# buffer.net
KiCad netlist of a schematic drawn in EAGLE
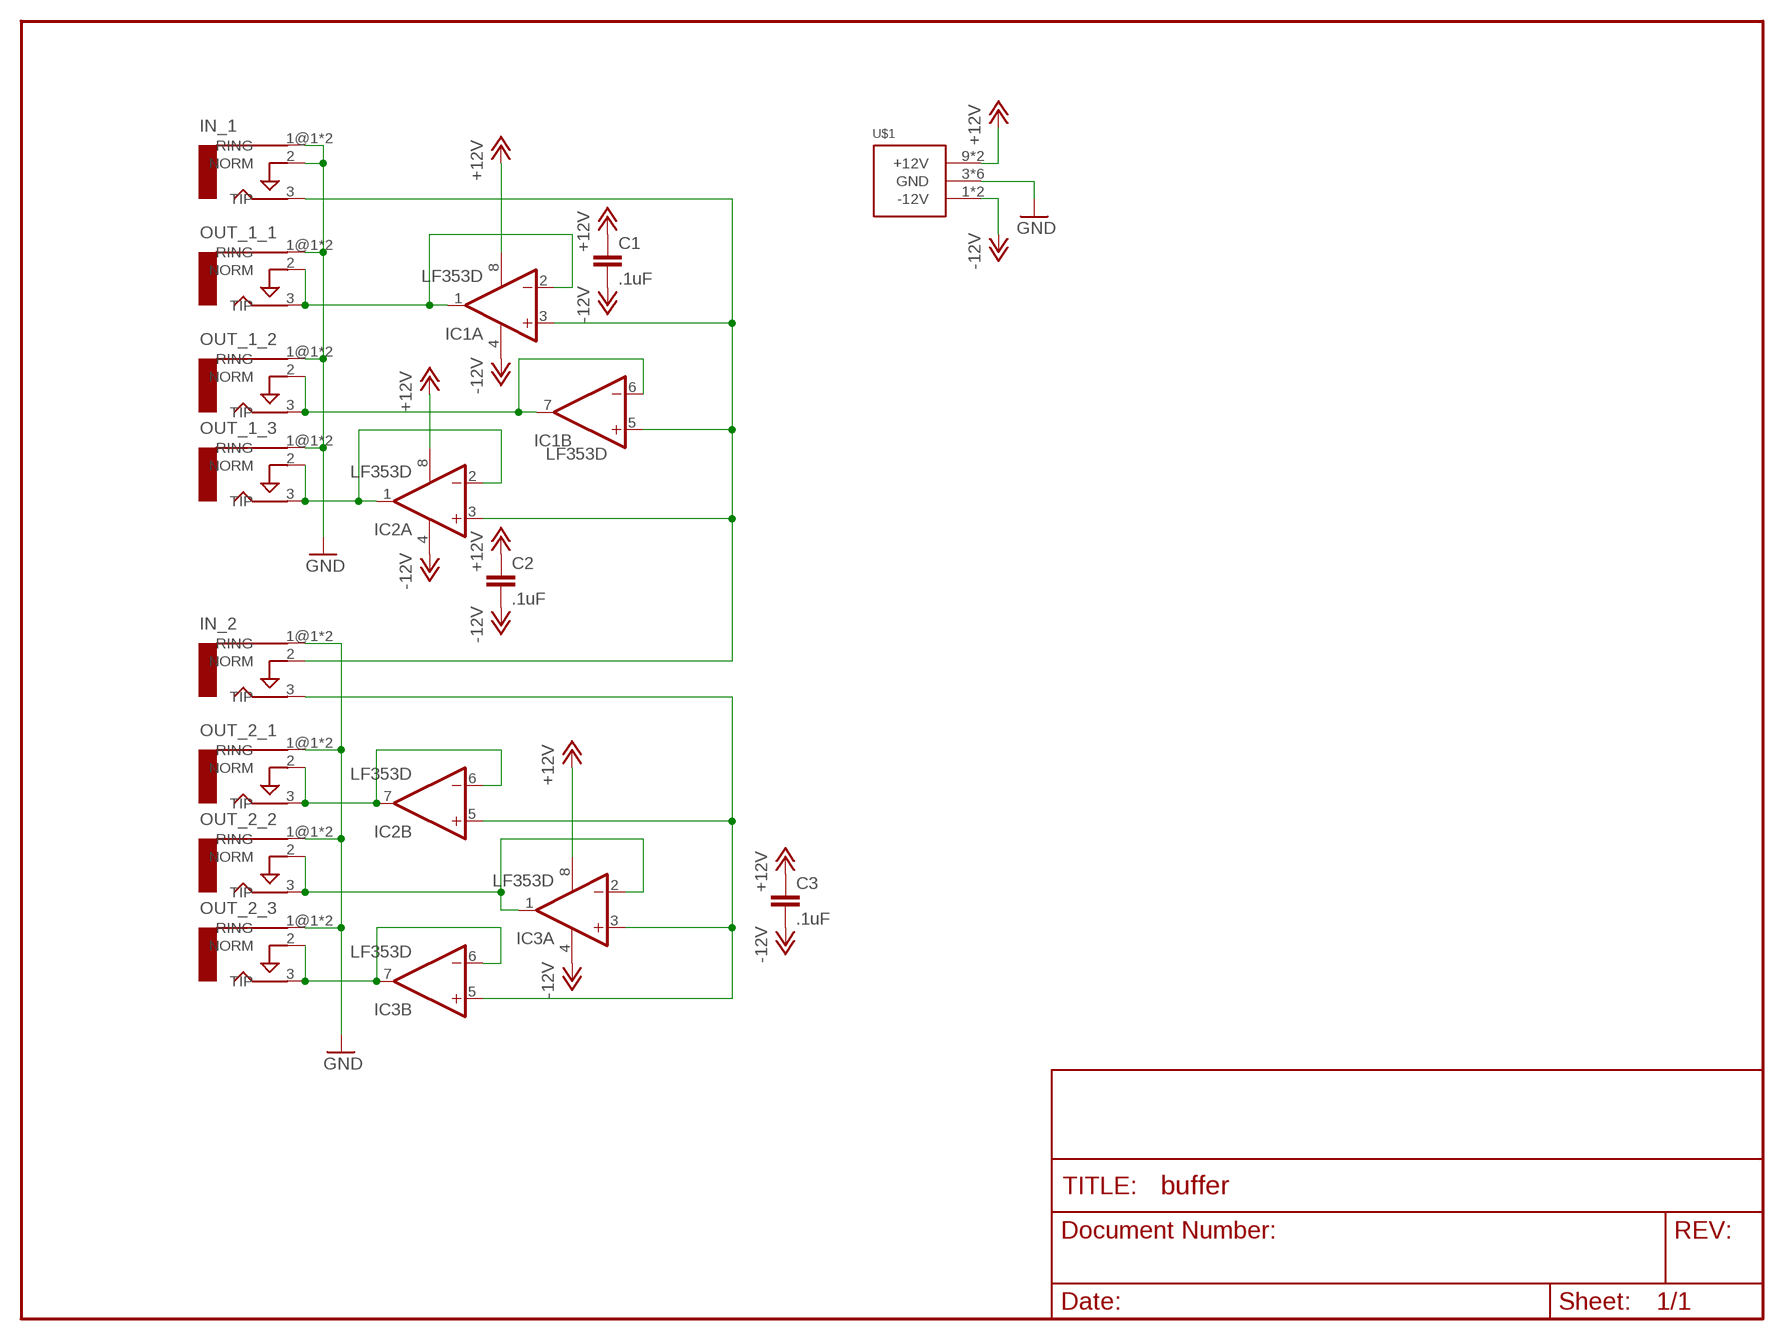
[diagram p0: schematic, sheet 1]

(export (version "E")
  (design (tool "Eeschema 10.0.6"))
  (components
    (comp (ref "C1")
      (value ".1uF")
      (footprint "eagle-import:0603-CAP")
      (libsource (lib "eagle-import") (part "CAP0603-CAP"))
    )
    (comp (ref "C2")
      (value ".1uF")
      (footprint "eagle-import:0603-CAP")
      (libsource (lib "eagle-import") (part "CAP0603-CAP"))
    )
    (comp (ref "C3")
      (value ".1uF")
      (footprint "eagle-import:0603-CAP")
      (libsource (lib "eagle-import") (part "CAP0603-CAP"))
    )
    (comp (ref "IC1")
      (value "LF353D")
      (footprint "eagle-import:SO08")
      (libsource (lib "eagle-import") (part "LF353D"))
    )
    (comp (ref "IC2")
      (value "LF353D")
      (footprint "eagle-import:SO08")
      (libsource (lib "eagle-import") (part "LF353D"))
    )
    (comp (ref "IC3")
      (value "LF353D")
      (footprint "eagle-import:SO08")
      (libsource (lib "eagle-import") (part "LF353D"))
    )
    (comp (ref "IN_1")
      (value "AUDIO-JACKERTHENVAR")
      (footprint "eagle-import:ERTHENVAR-JACK")
      (libsource (lib "eagle-import") (part "AUDIO-JACKERTHENVAR"))
    )
    (comp (ref "IN_2")
      (value "AUDIO-JACKERTHENVAR")
      (footprint "eagle-import:ERTHENVAR-JACK")
      (libsource (lib "eagle-import") (part "AUDIO-JACKERTHENVAR"))
    )
    (comp (ref "OUT_1_1")
      (value "AUDIO-JACKERTHENVAR")
      (footprint "eagle-import:ERTHENVAR-JACK")
      (libsource (lib "eagle-import") (part "AUDIO-JACKERTHENVAR"))
    )
    (comp (ref "OUT_1_2")
      (value "AUDIO-JACKERTHENVAR")
      (footprint "eagle-import:ERTHENVAR-JACK")
      (libsource (lib "eagle-import") (part "AUDIO-JACKERTHENVAR"))
    )
    (comp (ref "OUT_1_3")
      (value "AUDIO-JACKERTHENVAR")
      (footprint "eagle-import:ERTHENVAR-JACK")
      (libsource (lib "eagle-import") (part "AUDIO-JACKERTHENVAR"))
    )
    (comp (ref "OUT_2_1")
      (value "AUDIO-JACKERTHENVAR")
      (footprint "eagle-import:ERTHENVAR-JACK")
      (libsource (lib "eagle-import") (part "AUDIO-JACKERTHENVAR"))
    )
    (comp (ref "OUT_2_2")
      (value "AUDIO-JACKERTHENVAR")
      (footprint "eagle-import:ERTHENVAR-JACK")
      (libsource (lib "eagle-import") (part "AUDIO-JACKERTHENVAR"))
    )
    (comp (ref "OUT_2_3")
      (value "AUDIO-JACKERTHENVAR")
      (footprint "eagle-import:ERTHENVAR-JACK")
      (libsource (lib "eagle-import") (part "AUDIO-JACKERTHENVAR"))
    )
    (comp (ref "U$1")
      (value "POWER_SIMPLE16")
      (footprint "eagle-import:POWER_16")
      (libsource (lib "eagle-import") (part "POWER_SIMPLE16"))
    )
  )
  (nets
    (net (code "1") (name "+12V") (class "Default")
      (node (ref "C1") (pin "1") (pinfunction "1_1") (pintype "passive"))
      (node (ref "C2") (pin "1") (pinfunction "1_1") (pintype "passive"))
      (node (ref "C3") (pin "1") (pinfunction "1_1") (pintype "passive"))
      (node (ref "IC1") (pin "8") (pinfunction "V+_8") (pintype "power_in"))
      (node (ref "IC2") (pin "8") (pinfunction "V+_8") (pintype "power_in"))
      (node (ref "IC3") (pin "8") (pinfunction "V+_8") (pintype "power_in"))
      (node (ref "U$1") (pin "10") (pinfunction "+12V_10") (pintype "bidirectional"))
      (node (ref "U$1") (pin "9") (pinfunction "+12V_9") (pintype "bidirectional"))
    )
    (net (code "2") (name "-12V") (class "Default")
      (node (ref "C1") (pin "2") (pinfunction "2_2") (pintype "passive"))
      (node (ref "C2") (pin "2") (pinfunction "2_2") (pintype "passive"))
      (node (ref "C3") (pin "2") (pinfunction "2_2") (pintype "passive"))
      (node (ref "IC1") (pin "4") (pinfunction "V-_4") (pintype "power_in"))
      (node (ref "IC2") (pin "4") (pinfunction "V-_4") (pintype "power_in"))
      (node (ref "IC3") (pin "4") (pinfunction "V-_4") (pintype "power_in"))
      (node (ref "U$1") (pin "1") (pinfunction "-12V_1") (pintype "bidirectional"))
      (node (ref "U$1") (pin "2") (pinfunction "-12V_2") (pintype "bidirectional"))
    )
    (net (code "3") (name "GND") (class "Default")
      (node (ref "IN_1") (pin "1@1") (pinfunction "RING_1@1") (pintype "bidirectional"))
      (node (ref "IN_1") (pin "1@2") (pinfunction "RING_1@2") (pintype "bidirectional"))
      (node (ref "IN_1") (pin "2") (pinfunction "NORM_2") (pintype "bidirectional"))
      (node (ref "IN_2") (pin "1@1") (pinfunction "RING_1@1") (pintype "bidirectional"))
      (node (ref "IN_2") (pin "1@2") (pinfunction "RING_1@2") (pintype "bidirectional"))
      (node (ref "OUT_1_1") (pin "1@1") (pinfunction "RING_1@1") (pintype "bidirectional"))
      (node (ref "OUT_1_1") (pin "1@2") (pinfunction "RING_1@2") (pintype "bidirectional"))
      (node (ref "OUT_1_2") (pin "1@1") (pinfunction "RING_1@1") (pintype "bidirectional"))
      (node (ref "OUT_1_2") (pin "1@2") (pinfunction "RING_1@2") (pintype "bidirectional"))
      (node (ref "OUT_1_3") (pin "1@1") (pinfunction "RING_1@1") (pintype "bidirectional"))
      (node (ref "OUT_1_3") (pin "1@2") (pinfunction "RING_1@2") (pintype "bidirectional"))
      (node (ref "OUT_2_1") (pin "1@1") (pinfunction "RING_1@1") (pintype "bidirectional"))
      (node (ref "OUT_2_1") (pin "1@2") (pinfunction "RING_1@2") (pintype "bidirectional"))
      (node (ref "OUT_2_2") (pin "1@1") (pinfunction "RING_1@1") (pintype "bidirectional"))
      (node (ref "OUT_2_2") (pin "1@2") (pinfunction "RING_1@2") (pintype "bidirectional"))
      (node (ref "OUT_2_3") (pin "1@1") (pinfunction "RING_1@1") (pintype "bidirectional"))
      (node (ref "OUT_2_3") (pin "1@2") (pinfunction "RING_1@2") (pintype "bidirectional"))
      (node (ref "U$1") (pin "3") (pinfunction "GND_3") (pintype "bidirectional"))
      (node (ref "U$1") (pin "4") (pinfunction "GND_4") (pintype "bidirectional"))
      (node (ref "U$1") (pin "5") (pinfunction "GND_5") (pintype "bidirectional"))
      (node (ref "U$1") (pin "6") (pinfunction "GND_6") (pintype "bidirectional"))
      (node (ref "U$1") (pin "7") (pinfunction "GND_7") (pintype "bidirectional"))
      (node (ref "U$1") (pin "8") (pinfunction "GND_8") (pintype "bidirectional"))
    )
    (net (code "4") (name "Net-(IC1A-+IN)") (class "Default")
      (node (ref "IC1") (pin "3") (pinfunction "+IN_3") (pintype "input"))
      (node (ref "IC1") (pin "5") (pinfunction "+IN_5") (pintype "input"))
      (node (ref "IC2") (pin "3") (pinfunction "+IN_3") (pintype "input"))
      (node (ref "IN_1") (pin "3") (pinfunction "TIP_3") (pintype "bidirectional"))
      (node (ref "IN_2") (pin "2") (pinfunction "NORM_2") (pintype "bidirectional"))
    )
    (net (code "5") (name "Net-(IC1A--IN)") (class "Default")
      (node (ref "IC1") (pin "1") (pinfunction "OUT_1") (pintype "output"))
      (node (ref "IC1") (pin "2") (pinfunction "-IN_2") (pintype "input"))
      (node (ref "OUT_1_1") (pin "2") (pinfunction "NORM_2") (pintype "bidirectional"))
      (node (ref "OUT_1_1") (pin "3") (pinfunction "TIP_3") (pintype "bidirectional"))
    )
    (net (code "6") (name "Net-(IC1B--IN)") (class "Default")
      (node (ref "IC1") (pin "6") (pinfunction "-IN_6") (pintype "input"))
      (node (ref "IC1") (pin "7") (pinfunction "OUT_7") (pintype "output"))
      (node (ref "OUT_1_2") (pin "2") (pinfunction "NORM_2") (pintype "bidirectional"))
      (node (ref "OUT_1_2") (pin "3") (pinfunction "TIP_3") (pintype "bidirectional"))
    )
    (net (code "7") (name "Net-(IC2A--IN)") (class "Default")
      (node (ref "IC2") (pin "1") (pinfunction "OUT_1") (pintype "output"))
      (node (ref "IC2") (pin "2") (pinfunction "-IN_2") (pintype "input"))
      (node (ref "OUT_1_3") (pin "2") (pinfunction "NORM_2") (pintype "bidirectional"))
      (node (ref "OUT_1_3") (pin "3") (pinfunction "TIP_3") (pintype "bidirectional"))
    )
    (net (code "8") (name "Net-(IC2B-+IN)") (class "Default")
      (node (ref "IC2") (pin "5") (pinfunction "+IN_5") (pintype "input"))
      (node (ref "IC3") (pin "3") (pinfunction "+IN_3") (pintype "input"))
      (node (ref "IC3") (pin "5") (pinfunction "+IN_5") (pintype "input"))
      (node (ref "IN_2") (pin "3") (pinfunction "TIP_3") (pintype "bidirectional"))
    )
    (net (code "9") (name "Net-(IC2B--IN)") (class "Default")
      (node (ref "IC2") (pin "6") (pinfunction "-IN_6") (pintype "input"))
      (node (ref "IC2") (pin "7") (pinfunction "OUT_7") (pintype "output"))
      (node (ref "OUT_2_1") (pin "2") (pinfunction "NORM_2") (pintype "bidirectional"))
      (node (ref "OUT_2_1") (pin "3") (pinfunction "TIP_3") (pintype "bidirectional"))
    )
    (net (code "10") (name "Net-(IC3A--IN)") (class "Default")
      (node (ref "IC3") (pin "1") (pinfunction "OUT_1") (pintype "output"))
      (node (ref "IC3") (pin "2") (pinfunction "-IN_2") (pintype "input"))
      (node (ref "OUT_2_2") (pin "2") (pinfunction "NORM_2") (pintype "bidirectional"))
      (node (ref "OUT_2_2") (pin "3") (pinfunction "TIP_3") (pintype "bidirectional"))
    )
    (net (code "11") (name "Net-(IC3B--IN)") (class "Default")
      (node (ref "IC3") (pin "6") (pinfunction "-IN_6") (pintype "input"))
      (node (ref "IC3") (pin "7") (pinfunction "OUT_7") (pintype "output"))
      (node (ref "OUT_2_3") (pin "2") (pinfunction "NORM_2") (pintype "bidirectional"))
      (node (ref "OUT_2_3") (pin "3") (pinfunction "TIP_3") (pintype "bidirectional"))
    )
  )
)
